# board_v2.net
KiCad netlist of a schematic drawn in EAGLE
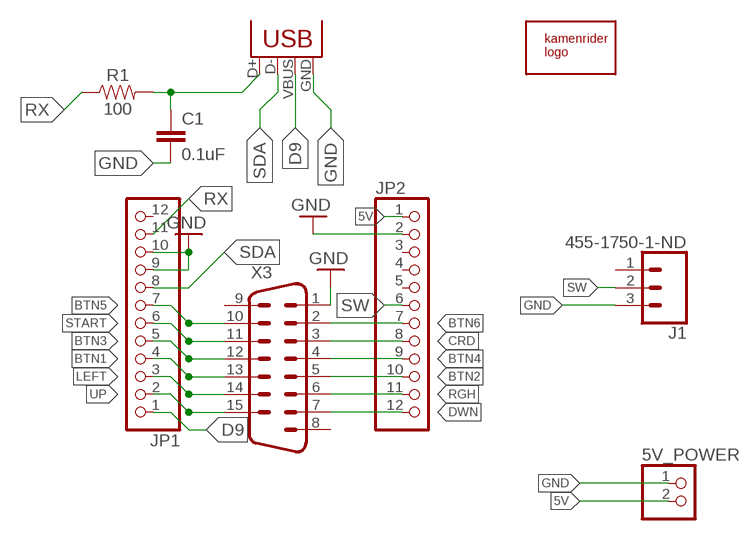
[diagram p0: schematic, sheet 1]

(export (version "E")
  (design (tool "Eeschema 10.0.6"))
  (components
    (comp (ref "5V_POWER")
      (value "PINHD-1X02_2.54-S")
      (footprint "eagle-import:1X02-S")
      (libsource (lib "eagle-import") (part "PINHD-1X02_2.54-S"))
    )
    (comp (ref "C1")
      (value "0.1uF")
      (footprint "eagle-import:0603")
      (libsource (lib "eagle-import") (part "0.1UF-0603-25V-5%"))
    )
    (comp (ref "J1")
      (value "455-1750-1-ND")
      (footprint "eagle-import:1X03")
      (libsource (lib "eagle-import") (part "CONN_03"))
    )
    (comp (ref "JP1")
      (value "PINHD-1X12")
      (footprint "eagle-import:1X12")
      (libsource (lib "eagle-import") (part "PINHD-1X12"))
    )
    (comp (ref "JP2")
      (value "PINHD-1X12")
      (footprint "eagle-import:1X12")
      (libsource (lib "eagle-import") (part "PINHD-1X12"))
    )
    (comp (ref "R1")
      (value "100")
      (footprint "eagle-import:0603")
      (libsource (lib "eagle-import") (part "100OHM-0603-1/10W-1%"))
    )
    (comp (ref "U$1")
      (value "KAMENRIDER_LOGOV2_COLOR_OPAC")
      (footprint "eagle-import:10_6_V2")
      (libsource (lib "eagle-import") (part "KAMENRIDER_LOGOV2_COLOR_OPAC"))
    )
    (comp (ref "X2")
      (value "USB-B-H")
      (footprint "eagle-import:USB-B-H")
      (libsource (lib "eagle-import") (part "USB-B-H"))
    )
    (comp (ref "X3")
      (value "M15V")
      (footprint "eagle-import:M15V")
      (libsource (lib "eagle-import") (part "M15V"))
    )
  )
  (nets
    (net (code "1") (name "5V") (class "Default")
      (node (ref "5V_POWER") (pin "2") (pinfunction "2_2") (pintype "passive"))
      (node (ref "JP2") (pin "1") (pinfunction "1_1") (pintype "passive"))
    )
    (net (code "2") (name "BTN1") (class "Default")
      (node (ref "JP1") (pin "4") (pinfunction "4_4") (pintype "passive"))
      (node (ref "X3") (pin "13") (pinfunction "13_13") (pintype "passive"))
    )
    (net (code "3") (name "BTN2") (class "Default")
      (node (ref "JP2") (pin "10") (pinfunction "10_10") (pintype "passive"))
      (node (ref "X3") (pin "5") (pinfunction "5_5") (pintype "passive"))
    )
    (net (code "4") (name "BTN3") (class "Default")
      (node (ref "JP1") (pin "5") (pinfunction "5_5") (pintype "passive"))
      (node (ref "X3") (pin "12") (pinfunction "12_12") (pintype "passive"))
    )
    (net (code "5") (name "BTN4") (class "Default")
      (node (ref "JP2") (pin "9") (pinfunction "9_9") (pintype "passive"))
      (node (ref "X3") (pin "4") (pinfunction "4_4") (pintype "passive"))
    )
    (net (code "6") (name "BTN5") (class "Default")
      (node (ref "JP1") (pin "7") (pinfunction "7_7") (pintype "passive"))
      (node (ref "X3") (pin "10") (pinfunction "10_10") (pintype "passive"))
    )
    (net (code "7") (name "BTN6") (class "Default")
      (node (ref "JP2") (pin "7") (pinfunction "7_7") (pintype "passive"))
      (node (ref "X3") (pin "2") (pinfunction "2_2") (pintype "passive"))
    )
    (net (code "8") (name "CRD") (class "Default")
      (node (ref "JP2") (pin "8") (pinfunction "8_8") (pintype "passive"))
      (node (ref "X3") (pin "3") (pinfunction "3_3") (pintype "passive"))
    )
    (net (code "9") (name "D9") (class "Default")
      (node (ref "JP1") (pin "1") (pinfunction "1_1") (pintype "passive"))
      (node (ref "X2") (pin "VBUS") (pinfunction "VBUS_VBUS") (pintype "bidirectional"))
    )
    (net (code "10") (name "DWN") (class "Default")
      (node (ref "JP2") (pin "12") (pinfunction "12_12") (pintype "passive"))
      (node (ref "X3") (pin "7") (pinfunction "7_7") (pintype "passive"))
    )
    (net (code "11") (name "GND") (class "Default")
      (node (ref "5V_POWER") (pin "1") (pinfunction "1_1") (pintype "passive"))
      (node (ref "C1") (pin "2") (pinfunction "2_2") (pintype "passive"))
      (node (ref "J1") (pin "3") (pinfunction "3_3") (pintype "passive"))
      (node (ref "JP1") (pin "10") (pinfunction "10_10") (pintype "passive"))
      (node (ref "JP1") (pin "9") (pinfunction "9_9") (pintype "passive"))
      (node (ref "JP2") (pin "2") (pinfunction "2_2") (pintype "passive"))
      (node (ref "X2") (pin "GND") (pinfunction "GND_GND") (pintype "bidirectional"))
      (node (ref "X3") (pin "1") (pinfunction "1_1") (pintype "passive"))
    )
    (net (code "12") (name "LEFT") (class "Default")
      (node (ref "JP1") (pin "3") (pinfunction "3_3") (pintype "passive"))
      (node (ref "X3") (pin "14") (pinfunction "14_14") (pintype "passive"))
    )
    (net (code "13") (name "Net-(C1-Pad1)") (class "Default")
      (node (ref "C1") (pin "1") (pinfunction "1_1") (pintype "passive"))
      (node (ref "R1") (pin "2") (pinfunction "2_2") (pintype "passive"))
      (node (ref "X2") (pin "D+") (pinfunction "D+_D+") (pintype "bidirectional"))
    )
    (net (code "14") (name "RGH") (class "Default")
      (node (ref "JP2") (pin "11") (pinfunction "11_11") (pintype "passive"))
      (node (ref "X3") (pin "6") (pinfunction "6_6") (pintype "passive"))
    )
    (net (code "15") (name "RX") (class "Default")
      (node (ref "JP1") (pin "11") (pinfunction "11_11") (pintype "passive"))
      (node (ref "R1") (pin "1") (pinfunction "1_1") (pintype "passive"))
    )
    (net (code "16") (name "SDA") (class "Default")
      (node (ref "JP1") (pin "8") (pinfunction "8_8") (pintype "passive"))
      (node (ref "X2") (pin "D-") (pinfunction "D-_D-") (pintype "bidirectional"))
    )
    (net (code "17") (name "START") (class "Default")
      (node (ref "JP1") (pin "6") (pinfunction "6_6") (pintype "passive"))
      (node (ref "X3") (pin "11") (pinfunction "11_11") (pintype "passive"))
    )
    (net (code "18") (name "SW") (class "Default")
      (node (ref "J1") (pin "2") (pinfunction "2_2") (pintype "passive"))
      (node (ref "JP2") (pin "6") (pinfunction "6_6") (pintype "passive"))
    )
    (net (code "19") (name "UP") (class "Default")
      (node (ref "JP1") (pin "2") (pinfunction "2_2") (pintype "passive"))
      (node (ref "X3") (pin "15") (pinfunction "15_15") (pintype "passive"))
    )
    (net (code "20") (name "unconnected-(J1-Pad1)") (class "Default")
      (node (ref "J1") (pin "1") (pinfunction "1_1") (pintype "passive"))
    )
    (net (code "21") (name "unconnected-(JP1-Pad12)") (class "Default")
      (node (ref "JP1") (pin "12") (pinfunction "12_12") (pintype "passive"))
    )
    (net (code "22") (name "unconnected-(JP2-Pad3)") (class "Default")
      (node (ref "JP2") (pin "3") (pinfunction "3_3") (pintype "passive"))
    )
    (net (code "23") (name "unconnected-(JP2-Pad4)") (class "Default")
      (node (ref "JP2") (pin "4") (pinfunction "4_4") (pintype "passive"))
    )
    (net (code "24") (name "unconnected-(JP2-Pad5)") (class "Default")
      (node (ref "JP2") (pin "5") (pinfunction "5_5") (pintype "passive"))
    )
    (net (code "25") (name "unconnected-(X3-Pad8)") (class "Default")
      (node (ref "X3") (pin "8") (pinfunction "8_8") (pintype "passive"))
    )
    (net (code "26") (name "unconnected-(X3-Pad9)") (class "Default")
      (node (ref "X3") (pin "9") (pinfunction "9_9") (pintype "passive"))
    )
  )
)
